# LVDS_IFC_VCO.net
KiCad netlist of a schematic drawn in Altium Designer
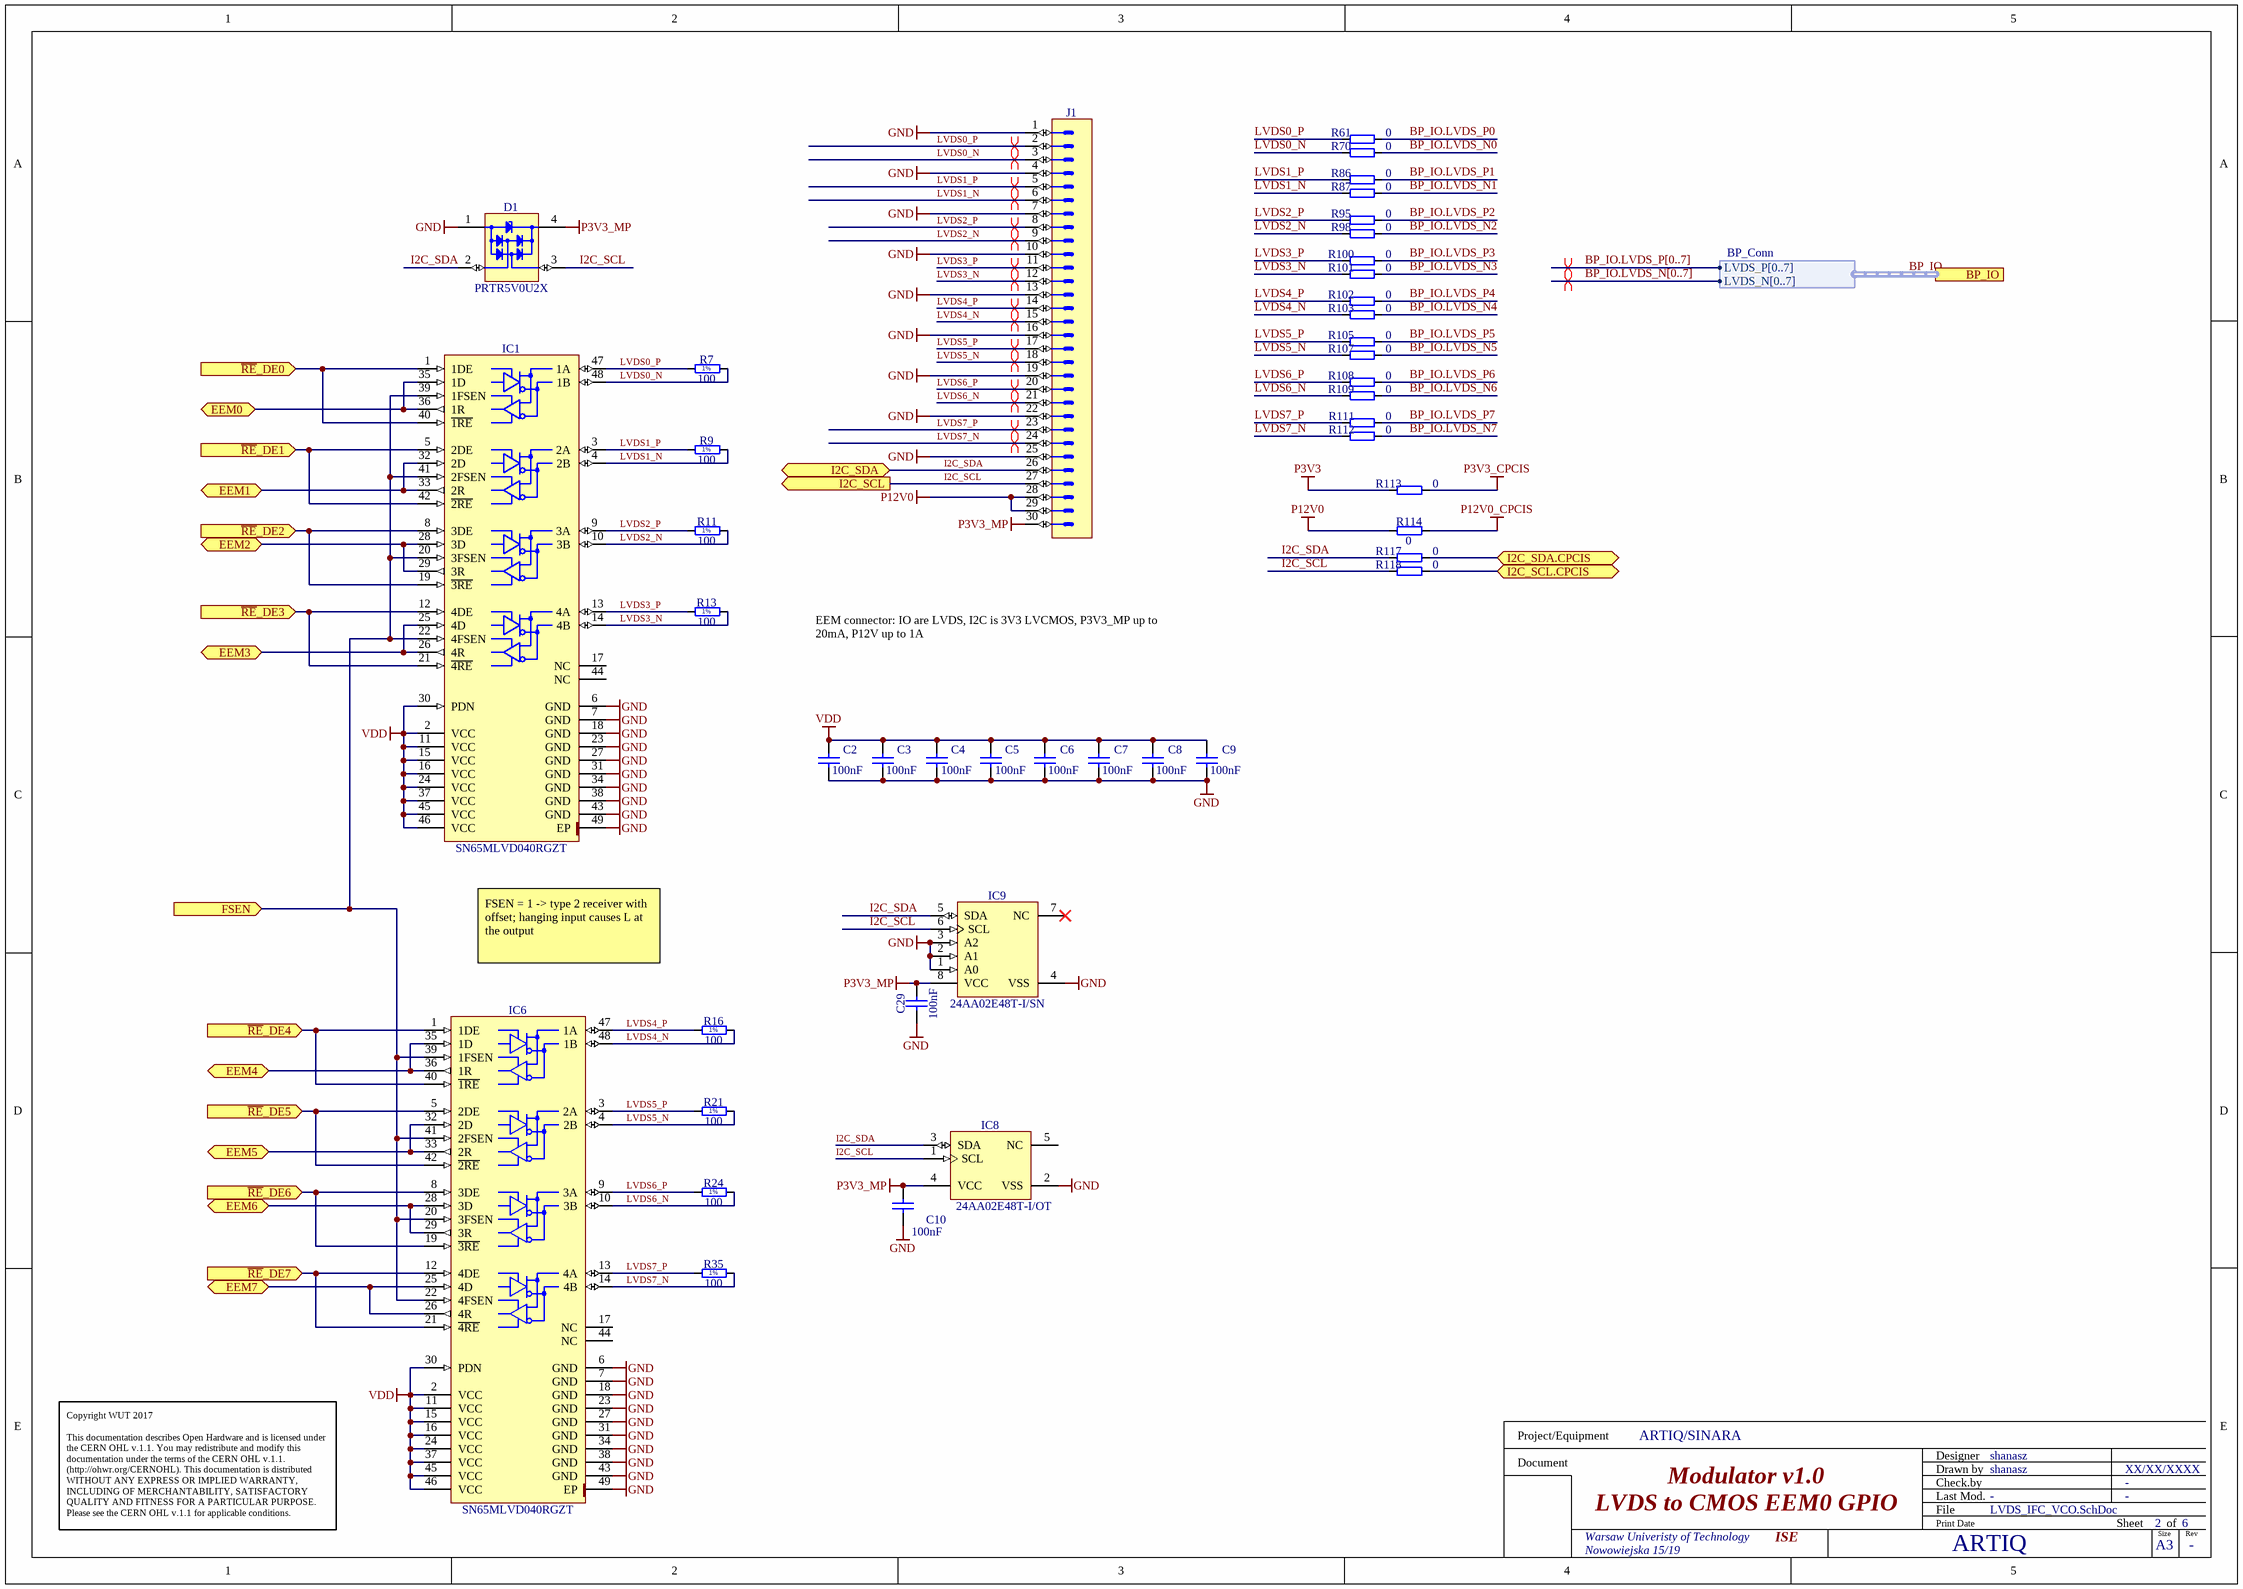
[diagram p0: LVDS_IFC_VCO.SchDoc]

(export (version "E")
  (design (tool "Eeschema 10.0.6"))
  (components
    (comp (ref "C2")
      (value "100nF")
      (footprint "CAPC1005X55N")
      (description "Non-polarised capacitor")
      (fields
        (field (name "PART NUMBER") "CC0402_100NF_16V_10%_X5R")
        (field (name "VOLTAGE") "16V")
        (field (name "AUTHOR") "CERN DEM JLC")
      )
      (libsource (lib "Capacitors") (part "Capacitor - non polarized"))
    )
    (comp (ref "C3")
      (value "100nF")
      (footprint "CAPC1005X55N")
      (description "Non-polarised capacitor")
      (fields
        (field (name "PART NUMBER") "CC0402_100NF_16V_10%_X5R")
        (field (name "VOLTAGE") "16V")
        (field (name "AUTHOR") "CERN DEM JLC")
      )
      (libsource (lib "Capacitors") (part "Capacitor - non polarized"))
    )
    (comp (ref "C4")
      (value "100nF")
      (footprint "CAPC1005X55N")
      (description "Non-polarised capacitor")
      (fields
        (field (name "PART NUMBER") "CC0402_100NF_16V_10%_X5R")
        (field (name "VOLTAGE") "16V")
        (field (name "AUTHOR") "CERN DEM JLC")
      )
      (libsource (lib "Capacitors") (part "Capacitor - non polarized"))
    )
    (comp (ref "C5")
      (value "100nF")
      (footprint "CAPC1005X55N")
      (description "Non-polarised capacitor")
      (fields
        (field (name "PART NUMBER") "CC0402_100NF_16V_10%_X5R")
        (field (name "VOLTAGE") "16V")
        (field (name "AUTHOR") "CERN DEM JLC")
      )
      (libsource (lib "Capacitors") (part "Capacitor - non polarized"))
    )
    (comp (ref "C6")
      (value "100nF")
      (footprint "CAPC1005X55N")
      (description "Non-polarised capacitor")
      (fields
        (field (name "PART NUMBER") "CC0402_100NF_16V_10%_X5R")
        (field (name "VOLTAGE") "16V")
        (field (name "AUTHOR") "CERN DEM JLC")
      )
      (libsource (lib "Capacitors") (part "Capacitor - non polarized"))
    )
    (comp (ref "C7")
      (value "100nF")
      (footprint "CAPC1005X55N")
      (description "Non-polarised capacitor")
      (fields
        (field (name "PART NUMBER") "CC0402_100NF_16V_10%_X5R")
        (field (name "VOLTAGE") "16V")
        (field (name "AUTHOR") "CERN DEM JLC")
      )
      (libsource (lib "Capacitors") (part "Capacitor - non polarized"))
    )
    (comp (ref "C8")
      (value "100nF")
      (footprint "CAPC1005X55N")
      (description "Non-polarised capacitor")
      (fields
        (field (name "PART NUMBER") "CC0402_100NF_16V_10%_X5R")
        (field (name "VOLTAGE") "16V")
        (field (name "AUTHOR") "CERN DEM JLC")
      )
      (libsource (lib "Capacitors") (part "Capacitor - non polarized"))
    )
    (comp (ref "C9")
      (value "100nF")
      (footprint "CAPC1005X55N")
      (description "Non-polarised capacitor")
      (fields
        (field (name "PART NUMBER") "CC0402_100NF_16V_10%_X5R")
        (field (name "VOLTAGE") "16V")
        (field (name "AUTHOR") "CERN DEM JLC")
      )
      (libsource (lib "Capacitors") (part "Capacitor - non polarized"))
    )
    (comp (ref "C10")
      (value "100nF")
      (footprint "CAPC1005X55N")
      (description "Non-polarised capacitor")
      (fields
        (field (name "PART NUMBER") "CC0402_100NF_16V_10%_X5R")
        (field (name "VOLTAGE") "16V")
        (field (name "AUTHOR") "CERN DEM JLC")
      )
      (libsource (lib "Capacitors") (part "Capacitor - non polarized"))
    )
    (comp (ref "C29")
      (value "100nF")
      (footprint "CAPC1005X55N")
      (description "Non-polarised capacitor")
      (fields
        (field (name "PART NUMBER") "CC0402_100NF_16V_10%_X5R")
        (field (name "VOLTAGE") "16V")
        (field (name "AUTHOR") "CERN DEM JLC")
      )
      (libsource (lib "Capacitors") (part "Capacitor - non polarized"))
    )
    (comp (ref "D1")
      (value "PRTR5V0U2X")
      (footprint "SOT190P230X110-4N")
      (description "Ultra Low Capacitance Double Rail-to-Rail ESD Protection Diode")
      (fields
        (field (name "VOLTAGE") "5.5V")
        (field (name "MANUFACTURER") "NXP SEMICONDUCTORS")
        (field (name "AUTHOR") "CERN DEM JLC")
      )
      (libsource (lib "ICs And Semiconductors") (part "PRTR5V0U2X"))
    )
    (comp (ref "IC1")
      (value "SN65MLVD040RGZT")
      (footprint "QFN50P700X700X100-49N-S420")
      (description "4-Channel Half-Duplex M-LVDS Line Transceiver")
      (fields (field (name "MANUFACTURER") "TEXAS INSTRUMENTS") (field (name "AUTHOR") "CERN DEM JLC"))
      (libsource (lib "ICs And Semiconductors") (part "SN65MLVD040"))
    )
    (comp (ref "IC6")
      (value "SN65MLVD040RGZT")
      (footprint "QFN50P700X700X100-49N-S420")
      (description "4-Channel Half-Duplex M-LVDS Line Transceiver")
      (fields (field (name "MANUFACTURER") "TEXAS INSTRUMENTS") (field (name "AUTHOR") "CERN DEM JLC"))
      (libsource (lib "ICs And Semiconductors") (part "SN65MLVD040"))
    )
    (comp (ref "IC8")
      (value "24AA02E48T-I/OT")
      (footprint "SOT95P280X145-5N")
      (description "1.7V-5.5V, 2K I2C Serial EEPROM With EUI-48 Node Identity")
      (fields (field (name "MANUFACTURER") "MICROCHIP TECHNOLOGY") (field (name "AUTHOR") "CERN DEM MR"))
      (libsource (lib "ICs And Semiconductors") (part "24AA02E48T-I/OT"))
    )
    (comp (ref "IC9")
      (value "24AA02E48T-I/SN")
      (footprint "SOIC127P600X175-8N")
      (description "1.7V-5.5V, 2K I2C™ Serial EEPROMs with EUI-48™ Node Identity")
      (fields (field (name "MANUFACTURER") "MICROCHIP TECHNOLOGY") (field (name "AUTHOR") "CERN DEM MR"))
      (libsource (lib "ICs And Semiconductors") (part "24AA025E48-I/SN"))
    )
    (comp (ref "J1")
      (value "~")
      (footprint "3M_N2530-6002RB")
      (description "Connector 30 Male")
      (fields
        (field (name "PART NUMBER") "3M_N2530-6002RB")
        (field (name "MANUFACTURER") "3M")
        (field (name "AUTHOR") "CERN DEM JLC")
      )
      (libsource (lib "Connectors") (part "Connector 30 Male"))
    )
    (comp (ref "R7")
      (value "100")
      (footprint "RESC1005X40N")
      (description "Resistor - 1%")
      (fields
        (field (name "PART NUMBER") "R0402_100R_1%_0.1W_100PPM")
        (field (name "POWER") "0.1W")
        (field (name "AUTHOR") "CERN DEM JLC")
      )
      (libsource (lib "Resistors") (part "Resistor - 1%"))
    )
    (comp (ref "R9")
      (value "100")
      (footprint "RESC1005X40N")
      (description "Resistor - 1%")
      (fields
        (field (name "PART NUMBER") "R0402_100R_1%_0.1W_100PPM")
        (field (name "POWER") "0.1W")
        (field (name "AUTHOR") "CERN DEM JLC")
      )
      (libsource (lib "Resistors") (part "Resistor - 1%"))
    )
    (comp (ref "R11")
      (value "100")
      (footprint "RESC1005X40N")
      (description "Resistor - 1%")
      (fields
        (field (name "PART NUMBER") "R0402_100R_1%_0.1W_100PPM")
        (field (name "POWER") "0.1W")
        (field (name "AUTHOR") "CERN DEM JLC")
      )
      (libsource (lib "Resistors") (part "Resistor - 1%"))
    )
    (comp (ref "R13")
      (value "100")
      (footprint "RESC1005X40N")
      (description "Resistor - 1%")
      (fields
        (field (name "PART NUMBER") "R0402_100R_1%_0.1W_100PPM")
        (field (name "POWER") "0.1W")
        (field (name "AUTHOR") "CERN DEM JLC")
      )
      (libsource (lib "Resistors") (part "Resistor - 1%"))
    )
    (comp (ref "R16")
      (value "100")
      (footprint "RESC1005X40N")
      (description "Resistor - 1%")
      (fields
        (field (name "PART NUMBER") "R0402_100R_1%_0.1W_100PPM")
        (field (name "POWER") "0.1W")
        (field (name "AUTHOR") "CERN DEM JLC")
      )
      (libsource (lib "Resistors") (part "Resistor - 1%"))
    )
    (comp (ref "R21")
      (value "100")
      (footprint "RESC1005X40N")
      (description "Resistor - 1%")
      (fields
        (field (name "PART NUMBER") "R0402_100R_1%_0.1W_100PPM")
        (field (name "POWER") "0.1W")
        (field (name "AUTHOR") "CERN DEM JLC")
      )
      (libsource (lib "Resistors") (part "Resistor - 1%"))
    )
    (comp (ref "R24")
      (value "100")
      (footprint "RESC1005X40N")
      (description "Resistor - 1%")
      (fields
        (field (name "PART NUMBER") "R0402_100R_1%_0.1W_100PPM")
        (field (name "POWER") "0.1W")
        (field (name "AUTHOR") "CERN DEM JLC")
      )
      (libsource (lib "Resistors") (part "Resistor - 1%"))
    )
    (comp (ref "R35")
      (value "100")
      (footprint "RESC1005X40N")
      (description "Resistor - 1%")
      (fields
        (field (name "PART NUMBER") "R0402_100R_1%_0.1W_100PPM")
        (field (name "POWER") "0.1W")
        (field (name "AUTHOR") "CERN DEM JLC")
      )
      (libsource (lib "Resistors") (part "Resistor - 1%"))
    )
    (comp (ref "R61")
      (value "0")
      (footprint "RESC1005X40N")
      (description "Resistor")
      (fields
        (field (name "PART NUMBER") "R0402_0R_JUMPER")
        (field (name "MANUFACTURER") "GENERIC")
        (field (name "AUTHOR") "CERN DEM JLC")
      )
      (libsource (lib "Resistors") (part "Resistor"))
    )
    (comp (ref "R70")
      (value "0")
      (footprint "RESC1005X40N")
      (description "Resistor")
      (fields
        (field (name "PART NUMBER") "R0402_0R_JUMPER")
        (field (name "MANUFACTURER") "GENERIC")
        (field (name "AUTHOR") "CERN DEM JLC")
      )
      (libsource (lib "Resistors") (part "Resistor"))
    )
    (comp (ref "R86")
      (value "0")
      (footprint "RESC1005X40N")
      (description "Resistor")
      (fields
        (field (name "PART NUMBER") "R0402_0R_JUMPER")
        (field (name "MANUFACTURER") "GENERIC")
        (field (name "AUTHOR") "CERN DEM JLC")
      )
      (libsource (lib "Resistors") (part "Resistor"))
    )
    (comp (ref "R87")
      (value "0")
      (footprint "RESC1005X40N")
      (description "Resistor")
      (fields
        (field (name "PART NUMBER") "R0402_0R_JUMPER")
        (field (name "MANUFACTURER") "GENERIC")
        (field (name "AUTHOR") "CERN DEM JLC")
      )
      (libsource (lib "Resistors") (part "Resistor"))
    )
    (comp (ref "R95")
      (value "0")
      (footprint "RESC1005X40N")
      (description "Resistor")
      (fields
        (field (name "PART NUMBER") "R0402_0R_JUMPER")
        (field (name "MANUFACTURER") "GENERIC")
        (field (name "AUTHOR") "CERN DEM JLC")
      )
      (libsource (lib "Resistors") (part "Resistor"))
    )
    (comp (ref "R98")
      (value "0")
      (footprint "RESC1005X40N")
      (description "Resistor")
      (fields
        (field (name "PART NUMBER") "R0402_0R_JUMPER")
        (field (name "MANUFACTURER") "GENERIC")
        (field (name "AUTHOR") "CERN DEM JLC")
      )
      (libsource (lib "Resistors") (part "Resistor"))
    )
    (comp (ref "R100")
      (value "0")
      (footprint "RESC1005X40N")
      (description "Resistor")
      (fields
        (field (name "PART NUMBER") "R0402_0R_JUMPER")
        (field (name "MANUFACTURER") "GENERIC")
        (field (name "AUTHOR") "CERN DEM JLC")
      )
      (libsource (lib "Resistors") (part "Resistor"))
    )
    (comp (ref "R101")
      (value "0")
      (footprint "RESC1005X40N")
      (description "Resistor")
      (fields
        (field (name "PART NUMBER") "R0402_0R_JUMPER")
        (field (name "MANUFACTURER") "GENERIC")
        (field (name "AUTHOR") "CERN DEM JLC")
      )
      (libsource (lib "Resistors") (part "Resistor"))
    )
    (comp (ref "R102")
      (value "0")
      (footprint "RESC1005X40N")
      (description "Resistor")
      (fields
        (field (name "PART NUMBER") "R0402_0R_JUMPER")
        (field (name "MANUFACTURER") "GENERIC")
        (field (name "AUTHOR") "CERN DEM JLC")
      )
      (libsource (lib "Resistors") (part "Resistor"))
    )
    (comp (ref "R103")
      (value "0")
      (footprint "RESC1005X40N")
      (description "Resistor")
      (fields
        (field (name "PART NUMBER") "R0402_0R_JUMPER")
        (field (name "MANUFACTURER") "GENERIC")
        (field (name "AUTHOR") "CERN DEM JLC")
      )
      (libsource (lib "Resistors") (part "Resistor"))
    )
    (comp (ref "R105")
      (value "0")
      (footprint "RESC1005X40N")
      (description "Resistor")
      (fields
        (field (name "PART NUMBER") "R0402_0R_JUMPER")
        (field (name "MANUFACTURER") "GENERIC")
        (field (name "AUTHOR") "CERN DEM JLC")
      )
      (libsource (lib "Resistors") (part "Resistor"))
    )
    (comp (ref "R107")
      (value "0")
      (footprint "RESC1005X40N")
      (description "Resistor")
      (fields
        (field (name "PART NUMBER") "R0402_0R_JUMPER")
        (field (name "MANUFACTURER") "GENERIC")
        (field (name "AUTHOR") "CERN DEM JLC")
      )
      (libsource (lib "Resistors") (part "Resistor"))
    )
    (comp (ref "R108")
      (value "0")
      (footprint "RESC1005X40N")
      (description "Resistor")
      (fields
        (field (name "PART NUMBER") "R0402_0R_JUMPER")
        (field (name "MANUFACTURER") "GENERIC")
        (field (name "AUTHOR") "CERN DEM JLC")
      )
      (libsource (lib "Resistors") (part "Resistor"))
    )
    (comp (ref "R109")
      (value "0")
      (footprint "RESC1005X40N")
      (description "Resistor")
      (fields
        (field (name "PART NUMBER") "R0402_0R_JUMPER")
        (field (name "MANUFACTURER") "GENERIC")
        (field (name "AUTHOR") "CERN DEM JLC")
      )
      (libsource (lib "Resistors") (part "Resistor"))
    )
    (comp (ref "R111")
      (value "0")
      (footprint "RESC1005X40N")
      (description "Resistor")
      (fields
        (field (name "PART NUMBER") "R0402_0R_JUMPER")
        (field (name "MANUFACTURER") "GENERIC")
        (field (name "AUTHOR") "CERN DEM JLC")
      )
      (libsource (lib "Resistors") (part "Resistor"))
    )
    (comp (ref "R112")
      (value "0")
      (footprint "RESC1005X40N")
      (description "Resistor")
      (fields
        (field (name "PART NUMBER") "R0402_0R_JUMPER")
        (field (name "MANUFACTURER") "GENERIC")
        (field (name "AUTHOR") "CERN DEM JLC")
      )
      (libsource (lib "Resistors") (part "Resistor"))
    )
    (comp (ref "R113")
      (value "0")
      (footprint "RESC1005X40N")
      (description "Resistor")
      (fields
        (field (name "PART NUMBER") "R0402_0R_JUMPER")
        (field (name "MANUFACTURER") "GENERIC")
        (field (name "AUTHOR") "CERN DEM JLC")
      )
      (libsource (lib "Resistors") (part "Resistor"))
    )
    (comp (ref "R114")
      (value "0")
      (footprint "RESC2012X60N")
      (description "Resistor")
      (fields
        (field (name "PART NUMBER") "R0805_0R_JUMPER")
        (field (name "MANUFACTURER") "GENERIC")
        (field (name "AUTHOR") "CERN DEM JLC")
      )
      (libsource (lib "Resistors") (part "Resistor"))
    )
    (comp (ref "R117")
      (value "0")
      (footprint "RESC1005X40N")
      (description "Resistor")
      (fields
        (field (name "PART NUMBER") "R0402_0R_JUMPER")
        (field (name "MANUFACTURER") "GENERIC")
        (field (name "AUTHOR") "CERN DEM JLC")
      )
      (libsource (lib "Resistors") (part "Resistor"))
    )
    (comp (ref "R118")
      (value "0")
      (footprint "RESC1005X40N")
      (description "Resistor")
      (fields
        (field (name "PART NUMBER") "R0402_0R_JUMPER")
        (field (name "MANUFACTURER") "GENERIC")
        (field (name "AUTHOR") "CERN DEM JLC")
      )
      (libsource (lib "Resistors") (part "Resistor"))
    )
  )
  (nets
    (net (code "2") (name "/BP_IO.LVDS_N0") (class "Default")
      (node (ref "R70") (pin "2") (pinfunction "2_2") (pintype "passive"))
    )
    (net (code "3") (name "/BP_IO.LVDS_N1") (class "Default")
      (node (ref "R87") (pin "2") (pinfunction "2_2") (pintype "passive"))
    )
    (net (code "4") (name "/BP_IO.LVDS_N2") (class "Default")
      (node (ref "R98") (pin "2") (pinfunction "2_2") (pintype "passive"))
    )
    (net (code "5") (name "/BP_IO.LVDS_N3") (class "Default")
      (node (ref "R101") (pin "2") (pinfunction "2_2") (pintype "passive"))
    )
    (net (code "6") (name "/BP_IO.LVDS_N4") (class "Default")
      (node (ref "R103") (pin "2") (pinfunction "2_2") (pintype "passive"))
    )
    (net (code "7") (name "/BP_IO.LVDS_N5") (class "Default")
      (node (ref "R107") (pin "2") (pinfunction "2_2") (pintype "passive"))
    )
    (net (code "8") (name "/BP_IO.LVDS_N6") (class "Default")
      (node (ref "R109") (pin "2") (pinfunction "2_2") (pintype "passive"))
    )
    (net (code "9") (name "/BP_IO.LVDS_N7") (class "Default")
      (node (ref "R112") (pin "2") (pinfunction "2_2") (pintype "passive"))
    )
    (net (code "10") (name "/BP_IO.LVDS_P0") (class "Default")
      (node (ref "R61") (pin "2") (pinfunction "2_2") (pintype "passive"))
    )
    (net (code "11") (name "/BP_IO.LVDS_P1") (class "Default")
      (node (ref "R86") (pin "2") (pinfunction "2_2") (pintype "passive"))
    )
    (net (code "12") (name "/BP_IO.LVDS_P2") (class "Default")
      (node (ref "R95") (pin "2") (pinfunction "2_2") (pintype "passive"))
    )
    (net (code "13") (name "/BP_IO.LVDS_P3") (class "Default")
      (node (ref "R100") (pin "2") (pinfunction "2_2") (pintype "passive"))
    )
    (net (code "14") (name "/BP_IO.LVDS_P4") (class "Default")
      (node (ref "R102") (pin "2") (pinfunction "2_2") (pintype "passive"))
    )
    (net (code "15") (name "/BP_IO.LVDS_P5") (class "Default")
      (node (ref "R105") (pin "2") (pinfunction "2_2") (pintype "passive"))
    )
    (net (code "16") (name "/BP_IO.LVDS_P6") (class "Default")
      (node (ref "R108") (pin "2") (pinfunction "2_2") (pintype "passive"))
    )
    (net (code "17") (name "/BP_IO.LVDS_P7") (class "Default")
      (node (ref "R111") (pin "2") (pinfunction "2_2") (pintype "passive"))
    )
    (net (code "19") (name "/EEM0") (class "Default")
      (node (ref "IC1") (pin "35") (pinfunction "1D_35") (pintype "input"))
      (node (ref "IC1") (pin "36") (pinfunction "1R_36") (pintype "output"))
    )
    (net (code "20") (name "/EEM1") (class "Default")
      (node (ref "IC1") (pin "32") (pinfunction "2D_32") (pintype "input"))
      (node (ref "IC1") (pin "33") (pinfunction "2R_33") (pintype "output"))
    )
    (net (code "21") (name "/EEM2") (class "Default")
      (node (ref "IC1") (pin "28") (pinfunction "3D_28") (pintype "input"))
      (node (ref "IC1") (pin "29") (pinfunction "3R_29") (pintype "output"))
    )
    (net (code "22") (name "/EEM3") (class "Default")
      (node (ref "IC1") (pin "25") (pinfunction "4D_25") (pintype "input"))
      (node (ref "IC1") (pin "26") (pinfunction "4R_26") (pintype "output"))
    )
    (net (code "23") (name "/EEM4") (class "Default")
      (node (ref "IC6") (pin "35") (pinfunction "1D_35") (pintype "input"))
      (node (ref "IC6") (pin "36") (pinfunction "1R_36") (pintype "output"))
    )
    (net (code "24") (name "/EEM5") (class "Default")
      (node (ref "IC6") (pin "32") (pinfunction "2D_32") (pintype "input"))
      (node (ref "IC6") (pin "33") (pinfunction "2R_33") (pintype "output"))
    )
    (net (code "25") (name "/EEM6") (class "Default")
      (node (ref "IC6") (pin "28") (pinfunction "3D_28") (pintype "input"))
      (node (ref "IC6") (pin "29") (pinfunction "3R_29") (pintype "output"))
    )
    (net (code "26") (name "/EEM7") (class "Default")
      (node (ref "IC6") (pin "25") (pinfunction "4D_25") (pintype "input"))
      (node (ref "IC6") (pin "26") (pinfunction "4R_26") (pintype "output"))
    )
    (net (code "27") (name "/FSEN") (class "Default")
      (node (ref "IC1") (pin "20") (pinfunction "3FSEN_20") (pintype "input"))
      (node (ref "IC1") (pin "22") (pinfunction "4FSEN_22") (pintype "input"))
      (node (ref "IC1") (pin "39") (pinfunction "1FSEN_39") (pintype "input"))
      (node (ref "IC1") (pin "41") (pinfunction "2FSEN_41") (pintype "input"))
      (node (ref "IC6") (pin "20") (pinfunction "3FSEN_20") (pintype "input"))
      (node (ref "IC6") (pin "22") (pinfunction "4FSEN_22") (pintype "input"))
      (node (ref "IC6") (pin "39") (pinfunction "1FSEN_39") (pintype "input"))
      (node (ref "IC6") (pin "41") (pinfunction "2FSEN_41") (pintype "input"))
    )
    (net (code "28") (name "/I2C_SCL") (class "Default")
      (node (ref "D1") (pin "3") (pinfunction "I/O2_3") (pintype "bidirectional"))
      (node (ref "IC8") (pin "1") (pinfunction "SCL_1") (pintype "input"))
      (node (ref "IC9") (pin "6") (pinfunction "SCL_6") (pintype "input"))
      (node (ref "J1") (pin "27") (pinfunction "27_27") (pintype "bidirectional"))
      (node (ref "R118") (pin "1") (pinfunction "1_1") (pintype "passive"))
    )
    (net (code "29") (name "/I2C_SCL.CPCIS") (class "Default")
      (node (ref "R118") (pin "2") (pinfunction "2_2") (pintype "passive"))
    )
    (net (code "30") (name "/I2C_SDA") (class "Default")
      (node (ref "D1") (pin "2") (pinfunction "I/O1_2") (pintype "bidirectional"))
      (node (ref "IC8") (pin "3") (pinfunction "SDA_3") (pintype "bidirectional"))
      (node (ref "IC9") (pin "5") (pinfunction "SDA_5") (pintype "bidirectional"))
      (node (ref "J1") (pin "26") (pinfunction "26_26") (pintype "bidirectional"))
      (node (ref "R117") (pin "1") (pinfunction "1_1") (pintype "passive"))
    )
    (net (code "31") (name "/I2C_SDA.CPCIS") (class "Default")
      (node (ref "R117") (pin "2") (pinfunction "2_2") (pintype "passive"))
    )
    (net (code "32") (name "/LVDS0_N") (class "Default")
      (node (ref "IC1") (pin "48") (pinfunction "1B_48") (pintype "bidirectional"))
      (node (ref "J1") (pin "3") (pinfunction "3_3") (pintype "bidirectional"))
      (node (ref "R7") (pin "2") (pinfunction "2_2") (pintype "passive"))
      (node (ref "R70") (pin "1") (pinfunction "1_1") (pintype "passive"))
    )
    (net (code "33") (name "/LVDS0_P") (class "Default")
      (node (ref "IC1") (pin "47") (pinfunction "1A_47") (pintype "bidirectional"))
      (node (ref "J1") (pin "2") (pinfunction "2_2") (pintype "bidirectional"))
      (node (ref "R61") (pin "1") (pinfunction "1_1") (pintype "passive"))
      (node (ref "R7") (pin "1") (pinfunction "1_1") (pintype "passive"))
    )
    (net (code "34") (name "/LVDS1_N") (class "Default")
      (node (ref "IC1") (pin "4") (pinfunction "2B_4") (pintype "bidirectional"))
      (node (ref "J1") (pin "6") (pinfunction "6_6") (pintype "bidirectional"))
      (node (ref "R87") (pin "1") (pinfunction "1_1") (pintype "passive"))
      (node (ref "R9") (pin "2") (pinfunction "2_2") (pintype "passive"))
    )
    (net (code "35") (name "/LVDS1_P") (class "Default")
      (node (ref "IC1") (pin "3") (pinfunction "2A_3") (pintype "bidirectional"))
      (node (ref "J1") (pin "5") (pinfunction "5_5") (pintype "bidirectional"))
      (node (ref "R86") (pin "1") (pinfunction "1_1") (pintype "passive"))
      (node (ref "R9") (pin "1") (pinfunction "1_1") (pintype "passive"))
    )
    (net (code "36") (name "/LVDS2_N") (class "Default")
      (node (ref "IC1") (pin "10") (pinfunction "3B_10") (pintype "bidirectional"))
      (node (ref "J1") (pin "9") (pinfunction "9_9") (pintype "bidirectional"))
      (node (ref "R11") (pin "2") (pinfunction "2_2") (pintype "passive"))
      (node (ref "R98") (pin "1") (pinfunction "1_1") (pintype "passive"))
    )
    (net (code "37") (name "/LVDS2_P") (class "Default")
      (node (ref "IC1") (pin "9") (pinfunction "3A_9") (pintype "bidirectional"))
      (node (ref "J1") (pin "8") (pinfunction "8_8") (pintype "bidirectional"))
      (node (ref "R11") (pin "1") (pinfunction "1_1") (pintype "passive"))
      (node (ref "R95") (pin "1") (pinfunction "1_1") (pintype "passive"))
    )
    (net (code "38") (name "/LVDS3_N") (class "Default")
      (node (ref "IC1") (pin "14") (pinfunction "4B_14") (pintype "bidirectional"))
      (node (ref "J1") (pin "12") (pinfunction "12_12") (pintype "bidirectional"))
      (node (ref "R101") (pin "1") (pinfunction "1_1") (pintype "passive"))
      (node (ref "R13") (pin "2") (pinfunction "2_2") (pintype "passive"))
    )
    (net (code "39") (name "/LVDS3_P") (class "Default")
      (node (ref "IC1") (pin "13") (pinfunction "4A_13") (pintype "bidirectional"))
      (node (ref "J1") (pin "11") (pinfunction "11_11") (pintype "bidirectional"))
      (node (ref "R100") (pin "1") (pinfunction "1_1") (pintype "passive"))
      (node (ref "R13") (pin "1") (pinfunction "1_1") (pintype "passive"))
    )
    (net (code "40") (name "/LVDS4_N") (class "Default")
      (node (ref "IC6") (pin "48") (pinfunction "1B_48") (pintype "bidirectional"))
      (node (ref "J1") (pin "15") (pinfunction "15_15") (pintype "bidirectional"))
      (node (ref "R103") (pin "1") (pinfunction "1_1") (pintype "passive"))
      (node (ref "R16") (pin "2") (pinfunction "2_2") (pintype "passive"))
    )
    (net (code "41") (name "/LVDS4_P") (class "Default")
      (node (ref "IC6") (pin "47") (pinfunction "1A_47") (pintype "bidirectional"))
      (node (ref "J1") (pin "14") (pinfunction "14_14") (pintype "bidirectional"))
      (node (ref "R102") (pin "1") (pinfunction "1_1") (pintype "passive"))
      (node (ref "R16") (pin "1") (pinfunction "1_1") (pintype "passive"))
    )
    (net (code "42") (name "/LVDS5_N") (class "Default")
      (node (ref "IC6") (pin "4") (pinfunction "2B_4") (pintype "bidirectional"))
      (node (ref "J1") (pin "18") (pinfunction "18_18") (pintype "bidirectional"))
      (node (ref "R107") (pin "1") (pinfunction "1_1") (pintype "passive"))
      (node (ref "R21") (pin "2") (pinfunction "2_2") (pintype "passive"))
    )
    (net (code "43") (name "/LVDS5_P") (class "Default")
      (node (ref "IC6") (pin "3") (pinfunction "2A_3") (pintype "bidirectional"))
      (node (ref "J1") (pin "17") (pinfunction "17_17") (pintype "bidirectional"))
      (node (ref "R105") (pin "1") (pinfunction "1_1") (pintype "passive"))
      (node (ref "R21") (pin "1") (pinfunction "1_1") (pintype "passive"))
    )
    (net (code "44") (name "/LVDS6_N") (class "Default")
      (node (ref "IC6") (pin "10") (pinfunction "3B_10") (pintype "bidirectional"))
      (node (ref "J1") (pin "21") (pinfunction "21_21") (pintype "bidirectional"))
      (node (ref "R109") (pin "1") (pinfunction "1_1") (pintype "passive"))
      (node (ref "R24") (pin "2") (pinfunction "2_2") (pintype "passive"))
    )
    (net (code "45") (name "/LVDS6_P") (class "Default")
      (node (ref "IC6") (pin "9") (pinfunction "3A_9") (pintype "bidirectional"))
      (node (ref "J1") (pin "20") (pinfunction "20_20") (pintype "bidirectional"))
      (node (ref "R108") (pin "1") (pinfunction "1_1") (pintype "passive"))
      (node (ref "R24") (pin "1") (pinfunction "1_1") (pintype "passive"))
    )
    (net (code "46") (name "/LVDS7_N") (class "Default")
      (node (ref "IC6") (pin "14") (pinfunction "4B_14") (pintype "bidirectional"))
      (node (ref "J1") (pin "24") (pinfunction "24_24") (pintype "bidirectional"))
      (node (ref "R112") (pin "1") (pinfunction "1_1") (pintype "passive"))
      (node (ref "R35") (pin "2") (pinfunction "2_2") (pintype "passive"))
    )
    (net (code "47") (name "/LVDS7_P") (class "Default")
      (node (ref "IC6") (pin "13") (pinfunction "4A_13") (pintype "bidirectional"))
      (node (ref "J1") (pin "23") (pinfunction "23_23") (pintype "bidirectional"))
      (node (ref "R111") (pin "1") (pinfunction "1_1") (pintype "passive"))
      (node (ref "R35") (pin "1") (pinfunction "1_1") (pintype "passive"))
    )
    (net (code "49") (name "/~{RE}_DE0") (class "Default")
      (node (ref "IC1") (pin "1") (pinfunction "1DE_1") (pintype "input"))
      (node (ref "IC1") (pin "40") (pinfunction "~{1RE}_40") (pintype "input"))
    )
    (net (code "50") (name "/~{RE}_DE1") (class "Default")
      (node (ref "IC1") (pin "42") (pinfunction "~{2RE}_42") (pintype "input"))
      (node (ref "IC1") (pin "5") (pinfunction "2DE_5") (pintype "input"))
    )
    (net (code "51") (name "/~{RE}_DE2") (class "Default")
      (node (ref "IC1") (pin "19") (pinfunction "~{3RE}_19") (pintype "input"))
      (node (ref "IC1") (pin "8") (pinfunction "3DE_8") (pintype "input"))
    )
    (net (code "52") (name "/~{RE}_DE3") (class "Default")
      (node (ref "IC1") (pin "12") (pinfunction "4DE_12") (pintype "input"))
      (node (ref "IC1") (pin "21") (pinfunction "~{4RE}_21") (pintype "input"))
    )
    (net (code "53") (name "/~{RE}_DE4") (class "Default")
      (node (ref "IC6") (pin "1") (pinfunction "1DE_1") (pintype "input"))
      (node (ref "IC6") (pin "40") (pinfunction "~{1RE}_40") (pintype "input"))
    )
    (net (code "54") (name "/~{RE}_DE5") (class "Default")
      (node (ref "IC6") (pin "42") (pinfunction "~{2RE}_42") (pintype "input"))
      (node (ref "IC6") (pin "5") (pinfunction "2DE_5") (pintype "input"))
    )
    (net (code "55") (name "/~{RE}_DE6") (class "Default")
      (node (ref "IC6") (pin "19") (pinfunction "~{3RE}_19") (pintype "input"))
      (node (ref "IC6") (pin "8") (pinfunction "3DE_8") (pintype "input"))
    )
    (net (code "56") (name "/~{RE}_DE7") (class "Default")
      (node (ref "IC6") (pin "12") (pinfunction "4DE_12") (pintype "input"))
      (node (ref "IC6") (pin "21") (pinfunction "~{4RE}_21") (pintype "input"))
    )
    (net (code "57") (name "GND") (class "Default")
      (node (ref "C10") (pin "1") (pinfunction "1_1") (pintype "passive"))
      (node (ref "C2") (pin "1") (pinfunction "1_1") (pintype "passive"))
      (node (ref "C29") (pin "1") (pinfunction "1_1") (pintype "passive"))
      (node (ref "C3") (pin "1") (pinfunction "1_1") (pintype "passive"))
      (node (ref "C4") (pin "1") (pinfunction "1_1") (pintype "passive"))
      (node (ref "C5") (pin "1") (pinfunction "1_1") (pintype "passive"))
      (node (ref "C6") (pin "1") (pinfunction "1_1") (pintype "passive"))
      (node (ref "C7") (pin "1") (pinfunction "1_1") (pintype "passive"))
      (node (ref "C8") (pin "1") (pinfunction "1_1") (pintype "passive"))
      (node (ref "C9") (pin "1") (pinfunction "1_1") (pintype "passive"))
      (node (ref "D1") (pin "1") (pinfunction "GND_1") (pintype "power_in"))
      (node (ref "IC1") (pin "18") (pinfunction "GND_18") (pintype "power_in"))
      (node (ref "IC1") (pin "23") (pinfunction "GND_23") (pintype "power_in"))
      (node (ref "IC1") (pin "27") (pinfunction "GND_27") (pintype "power_in"))
      (node (ref "IC1") (pin "31") (pinfunction "GND_31") (pintype "power_in"))
      (node (ref "IC1") (pin "34") (pinfunction "GND_34") (pintype "power_in"))
      (node (ref "IC1") (pin "38") (pinfunction "GND_38") (pintype "power_in"))
      (node (ref "IC1") (pin "43") (pinfunction "GND_43") (pintype "power_in"))
      (node (ref "IC1") (pin "49") (pinfunction "EP_49") (pintype "power_in"))
      (node (ref "IC1") (pin "6") (pinfunction "GND_6") (pintype "power_in"))
      (node (ref "IC1") (pin "7") (pinfunction "GND_7") (pintype "power_in"))
      (node (ref "IC6") (pin "18") (pinfunction "GND_18") (pintype "power_in"))
      (node (ref "IC6") (pin "23") (pinfunction "GND_23") (pintype "power_in"))
      (node (ref "IC6") (pin "27") (pinfunction "GND_27") (pintype "power_in"))
      (node (ref "IC6") (pin "31") (pinfunction "GND_31") (pintype "power_in"))
      (node (ref "IC6") (pin "34") (pinfunction "GND_34") (pintype "power_in"))
      (node (ref "IC6") (pin "38") (pinfunction "GND_38") (pintype "power_in"))
      (node (ref "IC6") (pin "43") (pinfunction "GND_43") (pintype "power_in"))
      (node (ref "IC6") (pin "49") (pinfunction "EP_49") (pintype "power_in"))
      (node (ref "IC6") (pin "6") (pinfunction "GND_6") (pintype "power_in"))
      (node (ref "IC6") (pin "7") (pinfunction "GND_7") (pintype "power_in"))
      (node (ref "IC8") (pin "2") (pinfunction "VSS_2") (pintype "power_in"))
      (node (ref "IC9") (pin "1") (pinfunction "A0_1") (pintype "input"))
      (node (ref "IC9") (pin "2") (pinfunction "A1_2") (pintype "input"))
      (node (ref "IC9") (pin "3") (pinfunction "A2_3") (pintype "input"))
      (node (ref "IC9") (pin "4") (pinfunction "VSS_4") (pintype "power_in"))
      (node (ref "J1") (pin "1") (pinfunction "1_1") (pintype "bidirectional"))
      (node (ref "J1") (pin "10") (pinfunction "10_10") (pintype "bidirectional"))
      (node (ref "J1") (pin "13") (pinfunction "13_13") (pintype "bidirectional"))
      (node (ref "J1") (pin "16") (pinfunction "16_16") (pintype "bidirectional"))
      (node (ref "J1") (pin "19") (pinfunction "19_19") (pintype "bidirectional"))
      (node (ref "J1") (pin "22") (pinfunction "22_22") (pintype "bidirectional"))
      (node (ref "J1") (pin "25") (pinfunction "25_25") (pintype "bidirectional"))
      (node (ref "J1") (pin "4") (pinfunction "4_4") (pintype "bidirectional"))
      (node (ref "J1") (pin "7") (pinfunction "7_7") (pintype "bidirectional"))
    )
    (net (code "58") (name "P3V3") (class "Default")
      (node (ref "R113") (pin "1") (pinfunction "1_1") (pintype "passive"))
    )
    (net (code "59") (name "P3V3_CPCIS") (class "Default")
      (node (ref "R113") (pin "2") (pinfunction "2_2") (pintype "passive"))
    )
    (net (code "60") (name "P3V3_MP") (class "Default")
      (node (ref "C10") (pin "2") (pinfunction "2_2") (pintype "passive"))
      (node (ref "C29") (pin "2") (pinfunction "2_2") (pintype "passive"))
      (node (ref "D1") (pin "4") (pinfunction "VCC_4") (pintype "power_in"))
      (node (ref "IC8") (pin "4") (pinfunction "VCC_4") (pintype "power_in"))
      (node (ref "IC9") (pin "8") (pinfunction "VCC_8") (pintype "power_in"))
      (node (ref "J1") (pin "30") (pinfunction "30_30") (pintype "bidirectional"))
    )
    (net (code "61") (name "P12V0") (class "Default")
      (node (ref "J1") (pin "28") (pinfunction "28_28") (pintype "bidirectional"))
      (node (ref "J1") (pin "29") (pinfunction "29_29") (pintype "bidirectional"))
      (node (ref "R114") (pin "1") (pinfunction "1_1") (pintype "passive"))
    )
    (net (code "62") (name "P12V0_CPCIS") (class "Default")
      (node (ref "R114") (pin "2") (pinfunction "2_2") (pintype "passive"))
    )
    (net (code "63") (name "VDD") (class "Default")
      (node (ref "C2") (pin "2") (pinfunction "2_2") (pintype "passive"))
      (node (ref "C3") (pin "2") (pinfunction "2_2") (pintype "passive"))
      (node (ref "C4") (pin "2") (pinfunction "2_2") (pintype "passive"))
      (node (ref "C5") (pin "2") (pinfunction "2_2") (pintype "passive"))
      (node (ref "C6") (pin "2") (pinfunction "2_2") (pintype "passive"))
      (node (ref "C7") (pin "2") (pinfunction "2_2") (pintype "passive"))
      (node (ref "C8") (pin "2") (pinfunction "2_2") (pintype "passive"))
      (node (ref "C9") (pin "2") (pinfunction "2_2") (pintype "passive"))
      (node (ref "IC1") (pin "11") (pinfunction "VCC_11") (pintype "power_in"))
      (node (ref "IC1") (pin "15") (pinfunction "VCC_15") (pintype "power_in"))
      (node (ref "IC1") (pin "16") (pinfunction "VCC_16") (pintype "power_in"))
      (node (ref "IC1") (pin "2") (pinfunction "VCC_2") (pintype "power_in"))
      (node (ref "IC1") (pin "24") (pinfunction "VCC_24") (pintype "power_in"))
      (node (ref "IC1") (pin "30") (pinfunction "PDN_30") (pintype "input"))
      (node (ref "IC1") (pin "37") (pinfunction "VCC_37") (pintype "power_in"))
      (node (ref "IC1") (pin "45") (pinfunction "VCC_45") (pintype "power_in"))
      (node (ref "IC1") (pin "46") (pinfunction "VCC_46") (pintype "power_in"))
      (node (ref "IC6") (pin "11") (pinfunction "VCC_11") (pintype "power_in"))
      (node (ref "IC6") (pin "15") (pinfunction "VCC_15") (pintype "power_in"))
      (node (ref "IC6") (pin "16") (pinfunction "VCC_16") (pintype "power_in"))
      (node (ref "IC6") (pin "2") (pinfunction "VCC_2") (pintype "power_in"))
      (node (ref "IC6") (pin "24") (pinfunction "VCC_24") (pintype "power_in"))
      (node (ref "IC6") (pin "30") (pinfunction "PDN_30") (pintype "input"))
      (node (ref "IC6") (pin "37") (pinfunction "VCC_37") (pintype "power_in"))
      (node (ref "IC6") (pin "45") (pinfunction "VCC_45") (pintype "power_in"))
      (node (ref "IC6") (pin "46") (pinfunction "VCC_46") (pintype "power_in"))
    )
    (net (code "64") (name "unconnected-(IC1-NC-Pad17)") (class "Default")
      (node (ref "IC1") (pin "17") (pinfunction "NC_17") (pintype "passive"))
    )
    (net (code "65") (name "unconnected-(IC1-NC-Pad44)") (class "Default")
      (node (ref "IC1") (pin "44") (pinfunction "NC_44") (pintype "passive"))
    )
    (net (code "66") (name "unconnected-(IC6-NC-Pad17)") (class "Default")
      (node (ref "IC6") (pin "17") (pinfunction "NC_17") (pintype "passive"))
    )
    (net (code "67") (name "unconnected-(IC6-NC-Pad44)") (class "Default")
      (node (ref "IC6") (pin "44") (pinfunction "NC_44") (pintype "passive"))
    )
    (net (code "68") (name "unconnected-(IC8-NC-Pad5)") (class "Default")
      (node (ref "IC8") (pin "5") (pinfunction "NC_5") (pintype "passive"))
    )
    (net (code "69") (name "unconnected-(IC9-NC-Pad7)") (class "Default")
      (node (ref "IC9") (pin "7") (pinfunction "NC_7") (pintype "passive+no_connect"))
    )
  )
)
